# VDMEDA_Arduino.net
KiCad netlist of a schematic drawn in Altium Designer
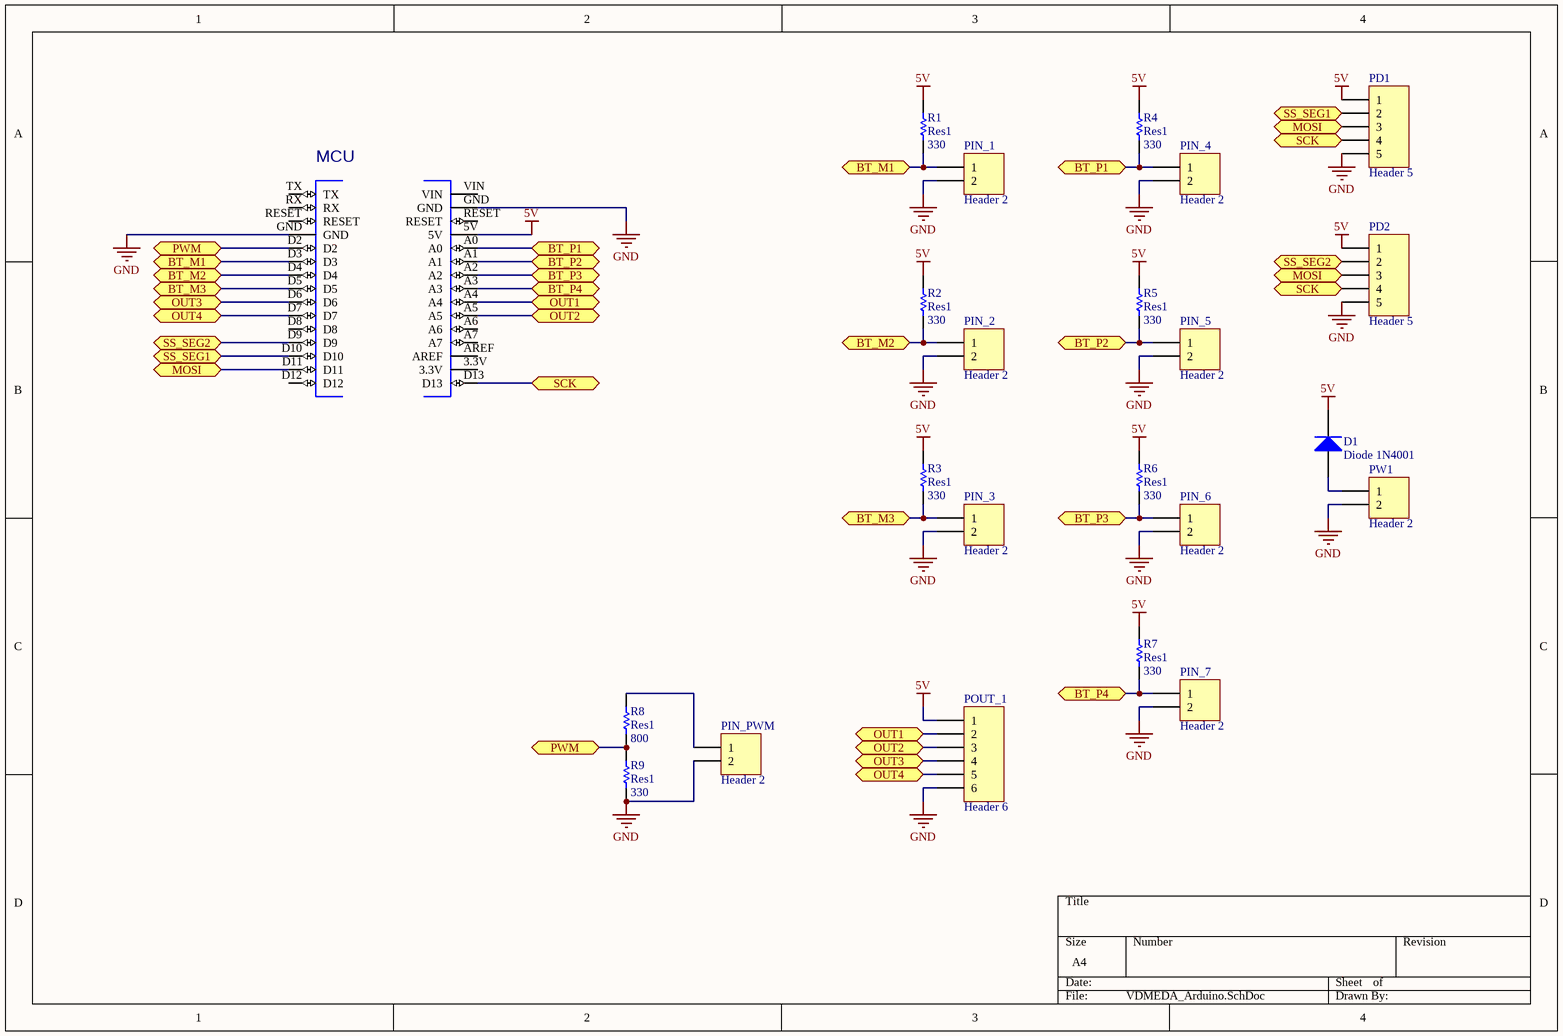
[diagram p0: VDMEDA_Arduino.SchDoc]

(export (version "E")
  (design (tool "Eeschema 10.0.6"))
  (components
    (comp (ref "D1")
      (value "Diode 1N4001")
      (footprint "DO-41")
      (description "1 Amp General Purpose Rectifier")
      (fields (field (name "PUBLISHER") "Altium Limited"))
      (libsource (lib "Miscellaneous Devices") (part "Diode 1N4001"))
    )
    (comp (ref "MCU")
      (value "ARDUINO_NANO")
      (footprint "ARDUINO_NANO_ARDUINO_NANO(Primary)")
      (libsource (lib "ARDUINO_NANO") (part "ARDUINO_NANO"))
    )
    (comp (ref "PD1")
      (value "Header 5")
      (footprint "HDR1X5")
      (description "Header, 5-Pin")
      (fields (field (name "PUBLISHER") "Altium Limited"))
      (libsource (lib "Miscellaneous Connectors") (part "Header 5"))
    )
    (comp (ref "PD2")
      (value "Header 5")
      (footprint "HDR1X5")
      (description "Header, 5-Pin")
      (fields (field (name "PUBLISHER") "Altium Limited"))
      (libsource (lib "Miscellaneous Connectors") (part "Header 5"))
    )
    (comp (ref "PIN_1")
      (value "Header 2")
      (footprint "HDR1X2")
      (description "Header, 2-Pin")
      (fields (field (name "PUBLISHER") "Altium Limited"))
      (libsource (lib "Miscellaneous Connectors") (part "Header 2"))
    )
    (comp (ref "PIN_2")
      (value "Header 2")
      (footprint "HDR1X2")
      (description "Header, 2-Pin")
      (fields (field (name "PUBLISHER") "Altium Limited"))
      (libsource (lib "Miscellaneous Connectors") (part "Header 2"))
    )
    (comp (ref "PIN_3")
      (value "Header 2")
      (footprint "HDR1X2")
      (description "Header, 2-Pin")
      (fields (field (name "PUBLISHER") "Altium Limited"))
      (libsource (lib "Miscellaneous Connectors") (part "Header 2"))
    )
    (comp (ref "PIN_4")
      (value "Header 2")
      (footprint "HDR1X2")
      (description "Header, 2-Pin")
      (fields (field (name "PUBLISHER") "Altium Limited"))
      (libsource (lib "Miscellaneous Connectors") (part "Header 2"))
    )
    (comp (ref "PIN_5")
      (value "Header 2")
      (footprint "HDR1X2")
      (description "Header, 2-Pin")
      (fields (field (name "PUBLISHER") "Altium Limited"))
      (libsource (lib "Miscellaneous Connectors") (part "Header 2"))
    )
    (comp (ref "PIN_6")
      (value "Header 2")
      (footprint "HDR1X2")
      (description "Header, 2-Pin")
      (fields (field (name "PUBLISHER") "Altium Limited"))
      (libsource (lib "Miscellaneous Connectors") (part "Header 2"))
    )
    (comp (ref "PIN_7")
      (value "Header 2")
      (footprint "HDR1X2")
      (description "Header, 2-Pin")
      (fields (field (name "PUBLISHER") "Altium Limited"))
      (libsource (lib "Miscellaneous Connectors") (part "Header 2"))
    )
    (comp (ref "PIN_PWM")
      (value "Header 2")
      (footprint "HDR1X2")
      (description "Header, 2-Pin")
      (fields (field (name "PUBLISHER") "Altium Limited"))
      (libsource (lib "Miscellaneous Connectors") (part "Header 2"))
    )
    (comp (ref "POUT_1")
      (value "Header 6")
      (footprint "HDR1X6")
      (description "Header, 6-Pin")
      (fields (field (name "PUBLISHER") "Altium Limited"))
      (libsource (lib "Miscellaneous Connectors") (part "Header 6"))
    )
    (comp (ref "PW1")
      (value "Header 2")
      (footprint "HDR1X2")
      (description "Header, 2-Pin")
      (fields (field (name "PUBLISHER") "Altium Limited"))
      (libsource (lib "Miscellaneous Connectors") (part "Header 2"))
    )
    (comp (ref "R1")
      (value "Res1")
      (footprint "AXIAL-0.3")
      (description "Resistor")
      (fields (field (name "ALTIUM_VALUE") "330") (field (name "PUBLISHER") "Altium Limited"))
      (libsource (lib "Miscellaneous Devices") (part "Res1"))
    )
    (comp (ref "R2")
      (value "Res1")
      (footprint "AXIAL-0.3")
      (description "Resistor")
      (fields (field (name "ALTIUM_VALUE") "330") (field (name "PUBLISHER") "Altium Limited"))
      (libsource (lib "Miscellaneous Devices") (part "Res1"))
    )
    (comp (ref "R3")
      (value "Res1")
      (footprint "AXIAL-0.3")
      (description "Resistor")
      (fields (field (name "ALTIUM_VALUE") "330") (field (name "PUBLISHER") "Altium Limited"))
      (libsource (lib "Miscellaneous Devices") (part "Res1"))
    )
    (comp (ref "R4")
      (value "Res1")
      (footprint "AXIAL-0.3")
      (description "Resistor")
      (fields (field (name "ALTIUM_VALUE") "330") (field (name "PUBLISHER") "Altium Limited"))
      (libsource (lib "Miscellaneous Devices") (part "Res1"))
    )
    (comp (ref "R5")
      (value "Res1")
      (footprint "AXIAL-0.3")
      (description "Resistor")
      (fields (field (name "ALTIUM_VALUE") "330") (field (name "PUBLISHER") "Altium Limited"))
      (libsource (lib "Miscellaneous Devices") (part "Res1"))
    )
    (comp (ref "R6")
      (value "Res1")
      (footprint "AXIAL-0.3")
      (description "Resistor")
      (fields (field (name "ALTIUM_VALUE") "330") (field (name "PUBLISHER") "Altium Limited"))
      (libsource (lib "Miscellaneous Devices") (part "Res1"))
    )
    (comp (ref "R7")
      (value "Res1")
      (footprint "AXIAL-0.3")
      (description "Resistor")
      (fields (field (name "ALTIUM_VALUE") "330") (field (name "PUBLISHER") "Altium Limited"))
      (libsource (lib "Miscellaneous Devices") (part "Res1"))
    )
    (comp (ref "R8")
      (value "Res1")
      (footprint "AXIAL-0.3")
      (description "Resistor")
      (fields (field (name "ALTIUM_VALUE") "800") (field (name "PUBLISHER") "Altium Limited"))
      (libsource (lib "Miscellaneous Devices") (part "Res1"))
    )
    (comp (ref "R9")
      (value "Res1")
      (footprint "AXIAL-0.3")
      (description "Resistor")
      (fields (field (name "ALTIUM_VALUE") "330") (field (name "PUBLISHER") "Altium Limited"))
      (libsource (lib "Miscellaneous Devices") (part "Res1"))
    )
  )
  (nets
    (net (code "1") (name "/BT_M1") (class "Default")
      (node (ref "MCU") (pin "D3") (pinfunction "D3_D3") (pintype "bidirectional"))
      (node (ref "PIN_1") (pin "1") (pinfunction "1_1") (pintype "passive"))
      (node (ref "R1") (pin "1") (pinfunction "1_1") (pintype "passive"))
    )
    (net (code "2") (name "/BT_M2") (class "Default")
      (node (ref "MCU") (pin "D4") (pinfunction "D4_D4") (pintype "bidirectional"))
      (node (ref "PIN_2") (pin "1") (pinfunction "1_1") (pintype "passive"))
      (node (ref "R2") (pin "1") (pinfunction "1_1") (pintype "passive"))
    )
    (net (code "3") (name "/BT_M3") (class "Default")
      (node (ref "MCU") (pin "D5") (pinfunction "D5_D5") (pintype "bidirectional"))
      (node (ref "PIN_3") (pin "1") (pinfunction "1_1") (pintype "passive"))
      (node (ref "R3") (pin "1") (pinfunction "1_1") (pintype "passive"))
    )
    (net (code "4") (name "/BT_P1") (class "Default")
      (node (ref "MCU") (pin "A0") (pinfunction "A0_A0") (pintype "bidirectional"))
      (node (ref "PIN_4") (pin "1") (pinfunction "1_1") (pintype "passive"))
      (node (ref "R4") (pin "1") (pinfunction "1_1") (pintype "passive"))
    )
    (net (code "5") (name "/BT_P2") (class "Default")
      (node (ref "MCU") (pin "A1") (pinfunction "A1_A1") (pintype "bidirectional"))
      (node (ref "PIN_5") (pin "1") (pinfunction "1_1") (pintype "passive"))
      (node (ref "R5") (pin "1") (pinfunction "1_1") (pintype "passive"))
    )
    (net (code "6") (name "/BT_P3") (class "Default")
      (node (ref "MCU") (pin "A2") (pinfunction "A2_A2") (pintype "bidirectional"))
      (node (ref "PIN_6") (pin "1") (pinfunction "1_1") (pintype "passive"))
      (node (ref "R6") (pin "1") (pinfunction "1_1") (pintype "passive"))
    )
    (net (code "7") (name "/BT_P4") (class "Default")
      (node (ref "MCU") (pin "A3") (pinfunction "A3_A3") (pintype "bidirectional"))
      (node (ref "PIN_7") (pin "1") (pinfunction "1_1") (pintype "passive"))
      (node (ref "R7") (pin "1") (pinfunction "1_1") (pintype "passive"))
    )
    (net (code "8") (name "/MOSI") (class "Default")
      (node (ref "MCU") (pin "D11") (pinfunction "D11_D11") (pintype "bidirectional"))
      (node (ref "PD1") (pin "3") (pinfunction "3_3") (pintype "passive"))
      (node (ref "PD2") (pin "3") (pinfunction "3_3") (pintype "passive"))
    )
    (net (code "9") (name "/OUT1") (class "Default")
      (node (ref "MCU") (pin "A4") (pinfunction "A4_A4") (pintype "bidirectional"))
      (node (ref "POUT_1") (pin "2") (pinfunction "2_2") (pintype "passive"))
    )
    (net (code "10") (name "/OUT2") (class "Default")
      (node (ref "MCU") (pin "A5") (pinfunction "A5_A5") (pintype "bidirectional"))
      (node (ref "POUT_1") (pin "3") (pinfunction "3_3") (pintype "passive"))
    )
    (net (code "11") (name "/OUT3") (class "Default")
      (node (ref "MCU") (pin "D6") (pinfunction "D6_D6") (pintype "bidirectional"))
      (node (ref "POUT_1") (pin "4") (pinfunction "4_4") (pintype "passive"))
    )
    (net (code "12") (name "/OUT4") (class "Default")
      (node (ref "MCU") (pin "D7") (pinfunction "D7_D7") (pintype "bidirectional"))
      (node (ref "POUT_1") (pin "5") (pinfunction "5_5") (pintype "passive"))
    )
    (net (code "13") (name "/PWM") (class "Default")
      (node (ref "MCU") (pin "D2") (pinfunction "D2_D2") (pintype "bidirectional"))
      (node (ref "R8") (pin "1") (pinfunction "1_1") (pintype "passive"))
      (node (ref "R9") (pin "2") (pinfunction "2_2") (pintype "passive"))
    )
    (net (code "14") (name "/SCK") (class "Default")
      (node (ref "MCU") (pin "D13") (pinfunction "D13_D13") (pintype "bidirectional"))
      (node (ref "PD1") (pin "4") (pinfunction "4_4") (pintype "passive"))
      (node (ref "PD2") (pin "4") (pinfunction "4_4") (pintype "passive"))
    )
    (net (code "15") (name "/SS_SEG1") (class "Default")
      (node (ref "MCU") (pin "D10") (pinfunction "D10_D10") (pintype "bidirectional"))
      (node (ref "PD1") (pin "2") (pinfunction "2_2") (pintype "passive"))
    )
    (net (code "16") (name "/SS_SEG2") (class "Default")
      (node (ref "MCU") (pin "D9") (pinfunction "D9_D9") (pintype "bidirectional"))
      (node (ref "PD2") (pin "2") (pinfunction "2_2") (pintype "passive"))
    )
    (net (code "17") (name "5V") (class "Default")
      (node (ref "D1") (pin "2") (pinfunction "K_2") (pintype "passive"))
      (node (ref "MCU") (pin "5V") (pinfunction "5V_5V") (pintype "power_in"))
      (node (ref "PD1") (pin "1") (pinfunction "1_1") (pintype "passive"))
      (node (ref "PD2") (pin "1") (pinfunction "1_1") (pintype "passive"))
      (node (ref "POUT_1") (pin "1") (pinfunction "1_1") (pintype "passive"))
      (node (ref "R1") (pin "2") (pinfunction "2_2") (pintype "passive"))
      (node (ref "R2") (pin "2") (pinfunction "2_2") (pintype "passive"))
      (node (ref "R3") (pin "2") (pinfunction "2_2") (pintype "passive"))
      (node (ref "R4") (pin "2") (pinfunction "2_2") (pintype "passive"))
      (node (ref "R5") (pin "2") (pinfunction "2_2") (pintype "passive"))
      (node (ref "R6") (pin "2") (pinfunction "2_2") (pintype "passive"))
      (node (ref "R7") (pin "2") (pinfunction "2_2") (pintype "passive"))
    )
    (net (code "18") (name "GND") (class "Default")
      (node (ref "MCU") (pin "GND") (pinfunction "GND_GND") (pintype "power_in"))
      (node (ref "PD1") (pin "5") (pinfunction "5_5") (pintype "passive"))
      (node (ref "PD2") (pin "5") (pinfunction "5_5") (pintype "passive"))
      (node (ref "PIN_1") (pin "2") (pinfunction "2_2") (pintype "passive"))
      (node (ref "PIN_2") (pin "2") (pinfunction "2_2") (pintype "passive"))
      (node (ref "PIN_3") (pin "2") (pinfunction "2_2") (pintype "passive"))
      (node (ref "PIN_4") (pin "2") (pinfunction "2_2") (pintype "passive"))
      (node (ref "PIN_5") (pin "2") (pinfunction "2_2") (pintype "passive"))
      (node (ref "PIN_6") (pin "2") (pinfunction "2_2") (pintype "passive"))
      (node (ref "PIN_7") (pin "2") (pinfunction "2_2") (pintype "passive"))
      (node (ref "PIN_PWM") (pin "2") (pinfunction "2_2") (pintype "passive"))
      (node (ref "POUT_1") (pin "6") (pinfunction "6_6") (pintype "passive"))
      (node (ref "PW1") (pin "2") (pinfunction "2_2") (pintype "passive"))
      (node (ref "R9") (pin "1") (pinfunction "1_1") (pintype "passive"))
    )
    (net (code "19") (name "Net-(D1-A)") (class "Default")
      (node (ref "D1") (pin "1") (pinfunction "A_1") (pintype "passive"))
      (node (ref "PW1") (pin "1") (pinfunction "1_1") (pintype "passive"))
    )
    (net (code "20") (name "Net-(PIN_PWM-Pad1)") (class "Default")
      (node (ref "PIN_PWM") (pin "1") (pinfunction "1_1") (pintype "passive"))
      (node (ref "R8") (pin "2") (pinfunction "2_2") (pintype "passive"))
    )
    (net (code "21") (name "unconnected-(MCU-Pad3.3V)") (class "Default")
      (node (ref "MCU") (pin "3.3V") (pinfunction "3.3V_3.3V") (pintype "power_in"))
    )
    (net (code "22") (name "unconnected-(MCU-PadA6)") (class "Default")
      (node (ref "MCU") (pin "A6") (pinfunction "A6_A6") (pintype "bidirectional"))
    )
    (net (code "23") (name "unconnected-(MCU-PadA7)") (class "Default")
      (node (ref "MCU") (pin "A7") (pinfunction "A7_A7") (pintype "bidirectional"))
    )
    (net (code "24") (name "unconnected-(MCU-PadAREF)") (class "Default")
      (node (ref "MCU") (pin "AREF") (pinfunction "AREF_AREF") (pintype "power_in"))
    )
    (net (code "25") (name "unconnected-(MCU-PadD8)") (class "Default")
      (node (ref "MCU") (pin "D8") (pinfunction "D8_D8") (pintype "bidirectional"))
    )
    (net (code "26") (name "unconnected-(MCU-PadD12)") (class "Default")
      (node (ref "MCU") (pin "D12") (pinfunction "D12_D12") (pintype "bidirectional"))
    )
    (net (code "27") (name "unconnected-(MCU-PadRESET)") (class "Default")
      (node (ref "MCU") (pin "RESET") (pinfunction "RESET_RESET") (pintype "bidirectional"))
    )
    (net (code "28") (name "unconnected-(MCU-PadRESET)_1") (class "Default")
      (node (ref "MCU") (pin "RESET") (pinfunction "RESET_RESET") (pintype "bidirectional"))
    )
    (net (code "29") (name "unconnected-(MCU-PadRX)") (class "Default")
      (node (ref "MCU") (pin "RX") (pinfunction "RX_RX") (pintype "bidirectional"))
    )
    (net (code "30") (name "unconnected-(MCU-PadTX)") (class "Default")
      (node (ref "MCU") (pin "TX") (pinfunction "TX_TX") (pintype "bidirectional"))
    )
    (net (code "31") (name "unconnected-(MCU-PadVIN)") (class "Default")
      (node (ref "MCU") (pin "VIN") (pinfunction "VIN_VIN") (pintype "power_in"))
    )
  )
)
